# Sheet.net
KiCad netlist of a schematic drawn in Altium Designer
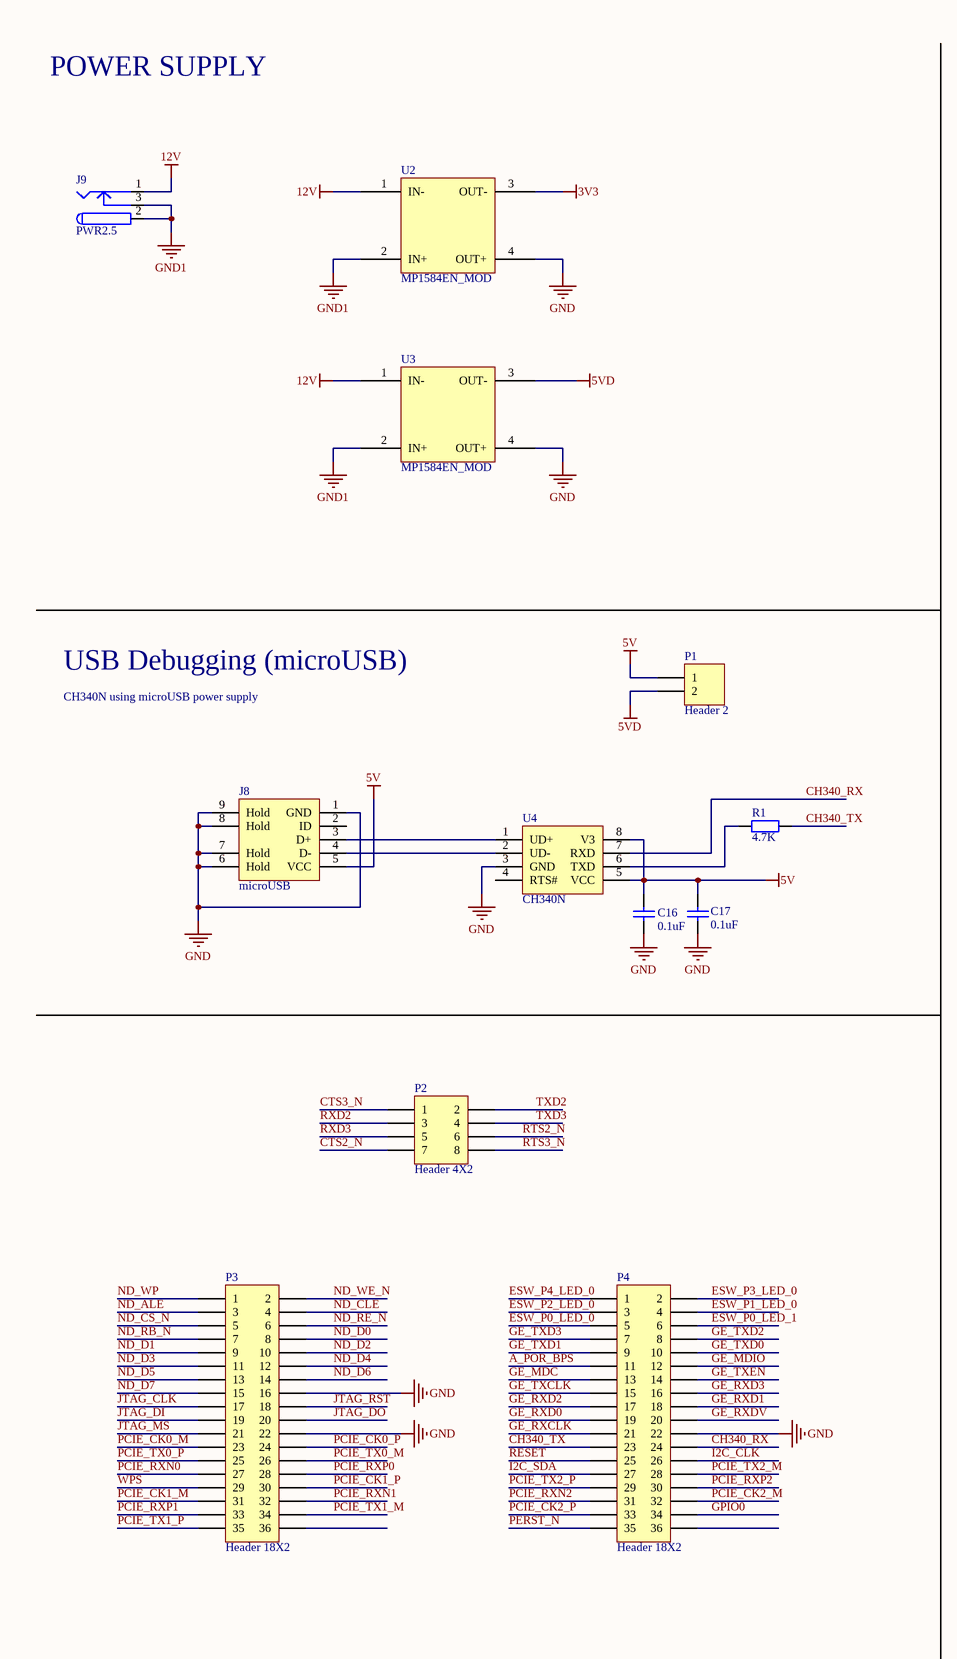
[diagram p0: Sheet.SchDoc, left]
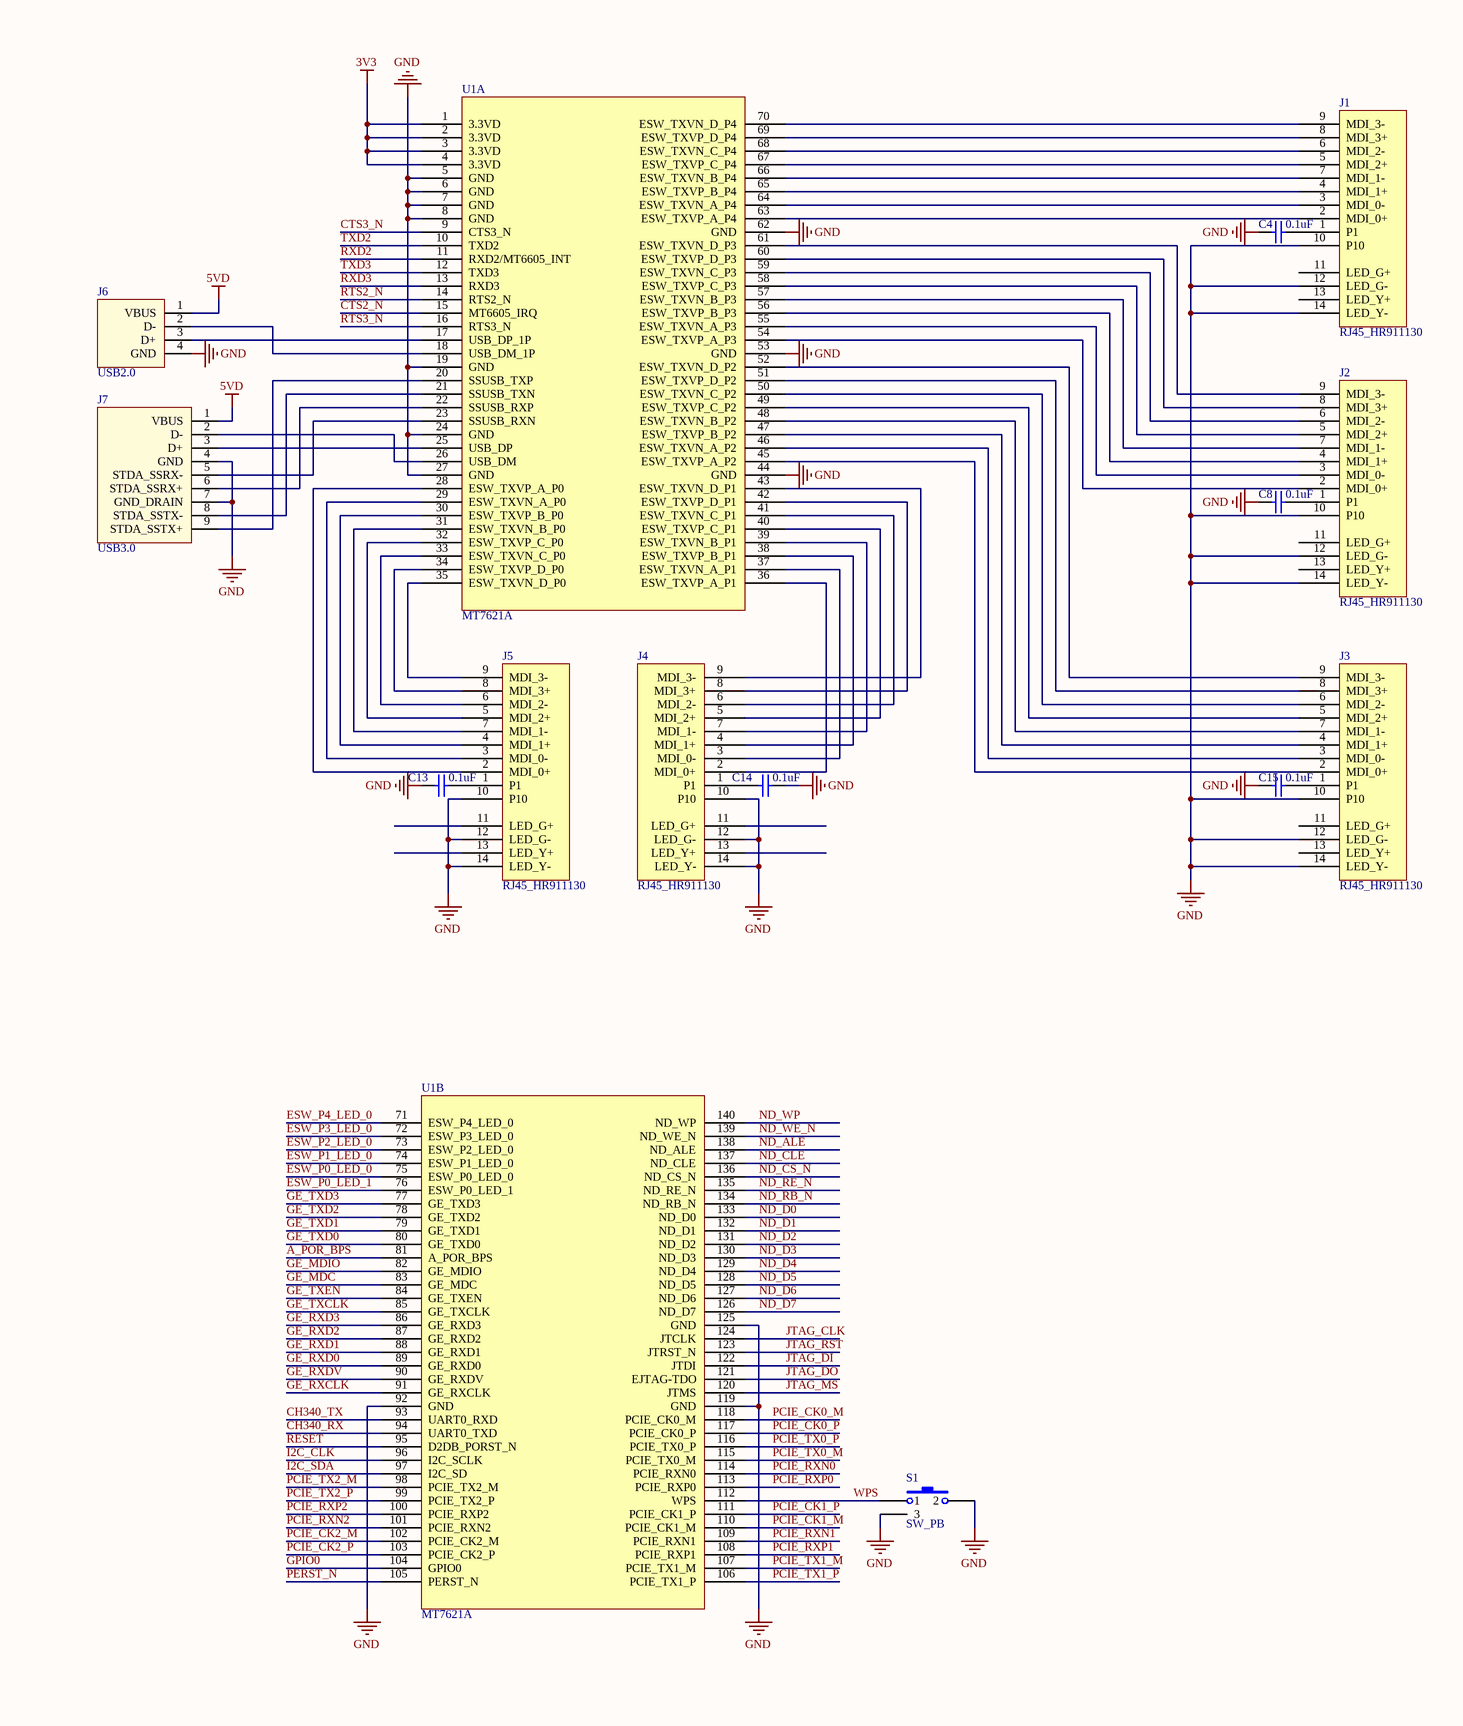
[diagram p1: Sheet.SchDoc, right]

(export (version "E")
  (design (tool "Eeschema 10.0.6"))
  (components
    (comp (ref "C4")
      (value "0.1uF")
      (footprint "C0603")
      (description "Capacitor")
      (fields (field (name "Comment") "Cap") (field (name "PUBLISHER") "Altium Limited"))
      (libsource (lib "Miscellaneous Devices") (part "Cap"))
    )
    (comp (ref "C8")
      (value "0.1uF")
      (footprint "C0603")
      (description "Capacitor")
      (fields (field (name "Comment") "Cap") (field (name "PUBLISHER") "Altium Limited"))
      (libsource (lib "Miscellaneous Devices") (part "Cap"))
    )
    (comp (ref "C13")
      (value "0.1uF")
      (footprint "C0603")
      (description "Capacitor")
      (fields (field (name "Comment") "Cap") (field (name "PUBLISHER") "Altium Limited"))
      (libsource (lib "Miscellaneous Devices") (part "Cap"))
    )
    (comp (ref "C14")
      (value "0.1uF")
      (footprint "C0603")
      (description "Capacitor")
      (fields (field (name "Comment") "Cap") (field (name "PUBLISHER") "Altium Limited"))
      (libsource (lib "Miscellaneous Devices") (part "Cap"))
    )
    (comp (ref "C15")
      (value "0.1uF")
      (footprint "C0603")
      (description "Capacitor")
      (fields (field (name "Comment") "Cap") (field (name "PUBLISHER") "Altium Limited"))
      (libsource (lib "Miscellaneous Devices") (part "Cap"))
    )
    (comp (ref "C16")
      (value "0.1uF")
      (footprint "C0603")
      (description "Capacitor")
      (fields (field (name "Comment") "Cap") (field (name "PUBLISHER") "Altium Limited"))
      (libsource (lib "Miscellaneous Devices") (part "Cap"))
    )
    (comp (ref "C17")
      (value "0.1uF")
      (footprint "C0603")
      (description "Capacitor")
      (fields (field (name "Comment") "Cap") (field (name "PUBLISHER") "Altium Limited"))
      (libsource (lib "Miscellaneous Devices") (part "Cap"))
    )
    (comp (ref "J1")
      (value "RJ45_HR911130")
      (footprint "RJ45_HR911130")
      (libsource (lib "") (part "RJ45_HR911130_1"))
    )
    (comp (ref "J2")
      (value "RJ45_HR911130")
      (footprint "RJ45_HR911130")
      (libsource (lib "") (part "RJ45_HR911130_1"))
    )
    (comp (ref "J3")
      (value "RJ45_HR911130")
      (footprint "RJ45_HR911130")
      (libsource (lib "") (part "RJ45_HR911130_1"))
    )
    (comp (ref "J4")
      (value "RJ45_HR911130")
      (footprint "RJ45_HR911130")
      (libsource (lib "7621_cmp") (part "RJ45_HR911130"))
    )
    (comp (ref "J5")
      (value "RJ45_HR911130")
      (footprint "RJ45_HR911130")
      (libsource (lib "") (part "RJ45_HR911130_1"))
    )
    (comp (ref "J6") (value "USB2.0") (footprint "USB2.0") (libsource (lib "7621_cmp") (part "USB2.0")))
    (comp (ref "J7") (value "USB3.0") (footprint "USB3.0") (libsource (lib "7621_cmp") (part "USB3.0")))
    (comp (ref "J8") (value "microUSB") (footprint "MICROusb") (libsource (lib "7621_cmp") (part "microUSB")))
    (comp (ref "J9")
      (value "PWR2.5")
      (footprint "CON\\DC-JACK\\4.7")
      (libsource (lib "7621_cmp") (part "PWR2.5"))
    )
    (comp (ref "P1")
      (value "Header 2")
      (footprint "HDR1X2")
      (description "Header, 2-Pin")
      (fields (field (name "PUBLISHER") "Altium Limited"))
      (libsource (lib "Miscellaneous Connectors") (part "Header 2"))
    )
    (comp (ref "P2")
      (value "Header 4X2")
      (footprint "HDR2X4")
      (description "Header, 4-Pin, Dual row")
      (fields (field (name "PUBLISHER") "Altium Limited"))
      (libsource (lib "Miscellaneous Connectors") (part "Header 4X2"))
    )
    (comp (ref "P3")
      (value "Header 18X2")
      (footprint "HDR2X18")
      (description "Header, 18-Pin, Dual row")
      (fields (field (name "PUBLISHER") "Altium Limited"))
      (libsource (lib "Miscellaneous Connectors") (part "Header 18X2"))
    )
    (comp (ref "P4")
      (value "Header 18X2")
      (footprint "HDR2X18")
      (description "Header, 18-Pin, Dual row")
      (fields (field (name "PUBLISHER") "Altium Limited"))
      (libsource (lib "Miscellaneous Connectors") (part "Header 18X2"))
    )
    (comp (ref "R1")
      (value "4.7K")
      (footprint "3-0603")
      (description "Resistor")
      (fields (field (name "Comment") "Res2") (field (name "PUBLISHER") "Altium Limited"))
      (libsource (lib "Miscellaneous Devices") (part "Res2"))
    )
    (comp (ref "S1") (value "SW_PB") (footprint "SW_PB") (libsource (lib "7621_cmp") (part "SW_PB")))
    (comp (ref "U1") (value "MT7621A") (footprint "HLK-7621") (libsource (lib "7621_cmp") (part "MT7621A")))
    (comp (ref "U2")
      (value "MP1584EN_MOD")
      (footprint "MP1584EN_MOD")
      (libsource (lib "7621_cmp") (part "MP1584EN_MOD"))
    )
    (comp (ref "U3")
      (value "MP1584EN_MOD")
      (footprint "MP1584EN_MOD")
      (libsource (lib "7621_cmp") (part "MP1584EN_MOD"))
    )
    (comp (ref "U4") (value "CH340N") (footprint "CH340N") (libsource (lib "7621_cmp") (part "CH340N")))
  )
  (nets
    (net (code "1") (name "/A_POR_BPS") (class "Default")
      (node (ref "P4") (pin "11") (pinfunction "11_11") (pintype "passive"))
      (node (ref "U1") (pin "81") (pinfunction "A_POR_BPS_81") (pintype "passive"))
    )
    (net (code "2") (name "/CH340_RX") (class "Default")
      (node (ref "P4") (pin "24") (pinfunction "24_24") (pintype "passive"))
      (node (ref "U1") (pin "94") (pinfunction "UART0_TXD_94") (pintype "passive"))
      (node (ref "U4") (pin "7") (pinfunction "RXD_7") (pintype "passive"))
    )
    (net (code "3") (name "/CH340_TX") (class "Default")
      (node (ref "P4") (pin "23") (pinfunction "23_23") (pintype "passive"))
      (node (ref "R1") (pin "1") (pinfunction "1_1") (pintype "passive"))
      (node (ref "U1") (pin "93") (pinfunction "UART0_RXD_93") (pintype "passive"))
    )
    (net (code "4") (name "/CTS2_N") (class "Default")
      (node (ref "P2") (pin "7") (pinfunction "7_7") (pintype "passive"))
      (node (ref "U1") (pin "15") (pinfunction "MT6605_IRQ_15") (pintype "passive"))
    )
    (net (code "5") (name "/CTS3_N") (class "Default")
      (node (ref "P2") (pin "1") (pinfunction "1_1") (pintype "passive"))
      (node (ref "U1") (pin "9") (pinfunction "CTS3_N_9") (pintype "passive"))
    )
    (net (code "6") (name "/ESW_P0_LED_0") (class "Default")
      (node (ref "P4") (pin "5") (pinfunction "5_5") (pintype "passive"))
      (node (ref "U1") (pin "75") (pinfunction "ESW_P0_LED_0_75") (pintype "passive"))
    )
    (net (code "7") (name "/ESW_P0_LED_1") (class "Default")
      (node (ref "P4") (pin "6") (pinfunction "6_6") (pintype "passive"))
      (node (ref "U1") (pin "76") (pinfunction "ESW_P0_LED_1_76") (pintype "passive"))
    )
    (net (code "8") (name "/ESW_P1_LED_0") (class "Default")
      (node (ref "P4") (pin "4") (pinfunction "4_4") (pintype "passive"))
      (node (ref "U1") (pin "74") (pinfunction "ESW_P1_LED_0_74") (pintype "passive"))
    )
    (net (code "9") (name "/ESW_P2_LED_0") (class "Default")
      (node (ref "P4") (pin "3") (pinfunction "3_3") (pintype "passive"))
      (node (ref "U1") (pin "73") (pinfunction "ESW_P2_LED_0_73") (pintype "passive"))
    )
    (net (code "10") (name "/ESW_P3_LED_0") (class "Default")
      (node (ref "P4") (pin "2") (pinfunction "2_2") (pintype "passive"))
      (node (ref "U1") (pin "72") (pinfunction "ESW_P3_LED_0_72") (pintype "passive"))
    )
    (net (code "11") (name "/ESW_P4_LED_0") (class "Default")
      (node (ref "P4") (pin "1") (pinfunction "1_1") (pintype "passive"))
      (node (ref "U1") (pin "71") (pinfunction "ESW_P4_LED_0_71") (pintype "passive"))
    )
    (net (code "12") (name "/GE_MDC") (class "Default")
      (node (ref "P4") (pin "13") (pinfunction "13_13") (pintype "passive"))
      (node (ref "U1") (pin "83") (pinfunction "GE_MDC_83") (pintype "passive"))
    )
    (net (code "13") (name "/GE_MDIO") (class "Default")
      (node (ref "P4") (pin "12") (pinfunction "12_12") (pintype "passive"))
      (node (ref "U1") (pin "82") (pinfunction "GE_MDIO_82") (pintype "passive"))
    )
    (net (code "14") (name "/GE_RXCLK") (class "Default")
      (node (ref "P4") (pin "21") (pinfunction "21_21") (pintype "passive"))
      (node (ref "U1") (pin "91") (pinfunction "GE_RXCLK_91") (pintype "passive"))
    )
    (net (code "15") (name "/GE_RXD0") (class "Default")
      (node (ref "P4") (pin "19") (pinfunction "19_19") (pintype "passive"))
      (node (ref "U1") (pin "89") (pinfunction "GE_RXD0_89") (pintype "passive"))
    )
    (net (code "16") (name "/GE_RXD1") (class "Default")
      (node (ref "P4") (pin "18") (pinfunction "18_18") (pintype "passive"))
      (node (ref "U1") (pin "88") (pinfunction "GE_RXD1_88") (pintype "passive"))
    )
    (net (code "17") (name "/GE_RXD2") (class "Default")
      (node (ref "P4") (pin "17") (pinfunction "17_17") (pintype "passive"))
      (node (ref "U1") (pin "87") (pinfunction "GE_RXD2_87") (pintype "passive"))
    )
    (net (code "18") (name "/GE_RXD3") (class "Default")
      (node (ref "P4") (pin "16") (pinfunction "16_16") (pintype "passive"))
      (node (ref "U1") (pin "86") (pinfunction "GE_RXD3_86") (pintype "passive"))
    )
    (net (code "19") (name "/GE_RXDV") (class "Default")
      (node (ref "P4") (pin "20") (pinfunction "20_20") (pintype "passive"))
      (node (ref "U1") (pin "90") (pinfunction "GE_RXDV_90") (pintype "passive"))
    )
    (net (code "20") (name "/GE_TXCLK") (class "Default")
      (node (ref "P4") (pin "15") (pinfunction "15_15") (pintype "passive"))
      (node (ref "U1") (pin "85") (pinfunction "GE_TXCLK_85") (pintype "passive"))
    )
    (net (code "21") (name "/GE_TXD0") (class "Default")
      (node (ref "P4") (pin "10") (pinfunction "10_10") (pintype "passive"))
      (node (ref "U1") (pin "80") (pinfunction "GE_TXD0_80") (pintype "passive"))
    )
    (net (code "22") (name "/GE_TXD1") (class "Default")
      (node (ref "P4") (pin "9") (pinfunction "9_9") (pintype "passive"))
      (node (ref "U1") (pin "79") (pinfunction "GE_TXD1_79") (pintype "passive"))
    )
    (net (code "23") (name "/GE_TXD2") (class "Default")
      (node (ref "P4") (pin "8") (pinfunction "8_8") (pintype "passive"))
      (node (ref "U1") (pin "78") (pinfunction "GE_TXD2_78") (pintype "passive"))
    )
    (net (code "24") (name "/GE_TXD3") (class "Default")
      (node (ref "P4") (pin "7") (pinfunction "7_7") (pintype "passive"))
      (node (ref "U1") (pin "77") (pinfunction "GE_TXD3_77") (pintype "passive"))
    )
    (net (code "25") (name "/GE_TXEN") (class "Default")
      (node (ref "P4") (pin "14") (pinfunction "14_14") (pintype "passive"))
      (node (ref "U1") (pin "84") (pinfunction "GE_TXEN_84") (pintype "passive"))
    )
    (net (code "26") (name "/GPIO0") (class "Default")
      (node (ref "P4") (pin "34") (pinfunction "34_34") (pintype "passive"))
      (node (ref "U1") (pin "104") (pinfunction "GPIO0_104") (pintype "passive"))
    )
    (net (code "27") (name "/I2C_CLK") (class "Default")
      (node (ref "P4") (pin "26") (pinfunction "26_26") (pintype "passive"))
      (node (ref "U1") (pin "96") (pinfunction "I2C_SCLK_96") (pintype "passive"))
    )
    (net (code "28") (name "/I2C_SDA") (class "Default")
      (node (ref "P4") (pin "27") (pinfunction "27_27") (pintype "passive"))
      (node (ref "U1") (pin "97") (pinfunction "I2C_SD_97") (pintype "passive"))
    )
    (net (code "29") (name "/JTAG_CLK") (class "Default")
      (node (ref "P3") (pin "17") (pinfunction "17_17") (pintype "passive"))
      (node (ref "U1") (pin "124") (pinfunction "JTCLK_124") (pintype "passive"))
    )
    (net (code "30") (name "/JTAG_DI") (class "Default")
      (node (ref "P3") (pin "19") (pinfunction "19_19") (pintype "passive"))
      (node (ref "U1") (pin "122") (pinfunction "JTDI_122") (pintype "passive"))
    )
    (net (code "31") (name "/JTAG_DO") (class "Default")
      (node (ref "P3") (pin "20") (pinfunction "20_20") (pintype "passive"))
      (node (ref "U1") (pin "121") (pinfunction "EJTAG-TDO_121") (pintype "passive"))
    )
    (net (code "32") (name "/JTAG_MS") (class "Default")
      (node (ref "P3") (pin "21") (pinfunction "21_21") (pintype "passive"))
      (node (ref "U1") (pin "120") (pinfunction "JTMS_120") (pintype "passive"))
    )
    (net (code "33") (name "/JTAG_RST") (class "Default")
      (node (ref "P3") (pin "18") (pinfunction "18_18") (pintype "passive"))
      (node (ref "U1") (pin "123") (pinfunction "JTRST_N_123") (pintype "passive"))
    )
    (net (code "34") (name "/ND_ALE") (class "Default")
      (node (ref "P3") (pin "3") (pinfunction "3_3") (pintype "passive"))
      (node (ref "U1") (pin "138") (pinfunction "ND_ALE_138") (pintype "passive"))
    )
    (net (code "35") (name "/ND_CLE") (class "Default")
      (node (ref "P3") (pin "4") (pinfunction "4_4") (pintype "passive"))
      (node (ref "U1") (pin "137") (pinfunction "ND_CLE_137") (pintype "passive"))
    )
    (net (code "36") (name "/ND_CS_N") (class "Default")
      (node (ref "P3") (pin "5") (pinfunction "5_5") (pintype "passive"))
      (node (ref "U1") (pin "136") (pinfunction "ND_CS_N_136") (pintype "passive"))
    )
    (net (code "37") (name "/ND_D0") (class "Default")
      (node (ref "P3") (pin "8") (pinfunction "8_8") (pintype "passive"))
      (node (ref "U1") (pin "133") (pinfunction "ND_D0_133") (pintype "passive"))
    )
    (net (code "38") (name "/ND_D1") (class "Default")
      (node (ref "P3") (pin "9") (pinfunction "9_9") (pintype "passive"))
      (node (ref "U1") (pin "132") (pinfunction "ND_D1_132") (pintype "passive"))
    )
    (net (code "39") (name "/ND_D2") (class "Default")
      (node (ref "P3") (pin "10") (pinfunction "10_10") (pintype "passive"))
      (node (ref "U1") (pin "131") (pinfunction "ND_D2_131") (pintype "passive"))
    )
    (net (code "40") (name "/ND_D3") (class "Default")
      (node (ref "P3") (pin "11") (pinfunction "11_11") (pintype "passive"))
      (node (ref "U1") (pin "130") (pinfunction "ND_D3_130") (pintype "passive"))
    )
    (net (code "41") (name "/ND_D4") (class "Default")
      (node (ref "P3") (pin "12") (pinfunction "12_12") (pintype "passive"))
      (node (ref "U1") (pin "129") (pinfunction "ND_D4_129") (pintype "passive"))
    )
    (net (code "42") (name "/ND_D5") (class "Default")
      (node (ref "P3") (pin "13") (pinfunction "13_13") (pintype "passive"))
      (node (ref "U1") (pin "128") (pinfunction "ND_D5_128") (pintype "passive"))
    )
    (net (code "43") (name "/ND_D6") (class "Default")
      (node (ref "P3") (pin "14") (pinfunction "14_14") (pintype "passive"))
      (node (ref "U1") (pin "127") (pinfunction "ND_D6_127") (pintype "passive"))
    )
    (net (code "44") (name "/ND_D7") (class "Default")
      (node (ref "P3") (pin "15") (pinfunction "15_15") (pintype "passive"))
      (node (ref "U1") (pin "126") (pinfunction "ND_D7_126") (pintype "passive"))
    )
    (net (code "45") (name "/ND_RB_N") (class "Default")
      (node (ref "P3") (pin "7") (pinfunction "7_7") (pintype "passive"))
      (node (ref "U1") (pin "134") (pinfunction "ND_RB_N_134") (pintype "passive"))
    )
    (net (code "46") (name "/ND_RE_N") (class "Default")
      (node (ref "P3") (pin "6") (pinfunction "6_6") (pintype "passive"))
      (node (ref "U1") (pin "135") (pinfunction "ND_RE_N_135") (pintype "passive"))
    )
    (net (code "47") (name "/ND_WE_N") (class "Default")
      (node (ref "P3") (pin "2") (pinfunction "2_2") (pintype "passive"))
      (node (ref "U1") (pin "139") (pinfunction "ND_WE_N_139") (pintype "passive"))
    )
    (net (code "48") (name "/ND_WP") (class "Default")
      (node (ref "P3") (pin "1") (pinfunction "1_1") (pintype "passive"))
      (node (ref "U1") (pin "140") (pinfunction "ND_WP_140") (pintype "passive"))
    )
    (net (code "49") (name "/PCIE_CK0_M") (class "Default")
      (node (ref "P3") (pin "23") (pinfunction "23_23") (pintype "passive"))
      (node (ref "U1") (pin "118") (pinfunction "PCIE_CK0_M_118") (pintype "passive"))
    )
    (net (code "50") (name "/PCIE_CK0_P") (class "Default")
      (node (ref "P3") (pin "24") (pinfunction "24_24") (pintype "passive"))
      (node (ref "U1") (pin "117") (pinfunction "PCIE_CK0_P_117") (pintype "passive"))
    )
    (net (code "51") (name "/PCIE_CK1_M") (class "Default")
      (node (ref "P3") (pin "31") (pinfunction "31_31") (pintype "passive"))
      (node (ref "U1") (pin "110") (pinfunction "PCIE_CK1_M_110") (pintype "passive"))
    )
    (net (code "52") (name "/PCIE_CK1_P") (class "Default")
      (node (ref "P3") (pin "30") (pinfunction "30_30") (pintype "passive"))
      (node (ref "U1") (pin "111") (pinfunction "PCIE_CK1_P_111") (pintype "passive"))
    )
    (net (code "53") (name "/PCIE_CK2_M") (class "Default")
      (node (ref "P4") (pin "32") (pinfunction "32_32") (pintype "passive"))
      (node (ref "U1") (pin "102") (pinfunction "PCIE_CK2_M_102") (pintype "passive"))
    )
    (net (code "54") (name "/PCIE_CK2_P") (class "Default")
      (node (ref "P4") (pin "33") (pinfunction "33_33") (pintype "passive"))
      (node (ref "U1") (pin "103") (pinfunction "PCIE_CK2_P_103") (pintype "passive"))
    )
    (net (code "55") (name "/PCIE_RXN0") (class "Default")
      (node (ref "P3") (pin "27") (pinfunction "27_27") (pintype "passive"))
      (node (ref "U1") (pin "114") (pinfunction "PCIE_RXN0_114") (pintype "passive"))
    )
    (net (code "56") (name "/PCIE_RXN1") (class "Default")
      (node (ref "P3") (pin "32") (pinfunction "32_32") (pintype "passive"))
      (node (ref "U1") (pin "109") (pinfunction "PCIE_RXN1_109") (pintype "passive"))
    )
    (net (code "57") (name "/PCIE_RXN2") (class "Default")
      (node (ref "P4") (pin "31") (pinfunction "31_31") (pintype "passive"))
      (node (ref "U1") (pin "101") (pinfunction "PCIE_RXN2_101") (pintype "passive"))
    )
    (net (code "58") (name "/PCIE_RXP0") (class "Default")
      (node (ref "P3") (pin "28") (pinfunction "28_28") (pintype "passive"))
      (node (ref "U1") (pin "113") (pinfunction "PCIE_RXP0_113") (pintype "passive"))
    )
    (net (code "59") (name "/PCIE_RXP1") (class "Default")
      (node (ref "P3") (pin "33") (pinfunction "33_33") (pintype "passive"))
      (node (ref "U1") (pin "108") (pinfunction "PCIE_RXP1_108") (pintype "passive"))
    )
    (net (code "60") (name "/PCIE_RXP2") (class "Default")
      (node (ref "P4") (pin "30") (pinfunction "30_30") (pintype "passive"))
      (node (ref "U1") (pin "100") (pinfunction "PCIE_RXP2_100") (pintype "passive"))
    )
    (net (code "61") (name "/PCIE_TX0_M") (class "Default")
      (node (ref "P3") (pin "26") (pinfunction "26_26") (pintype "passive"))
      (node (ref "U1") (pin "115") (pinfunction "PCIE_TX0_M_115") (pintype "passive"))
    )
    (net (code "62") (name "/PCIE_TX0_P") (class "Default")
      (node (ref "P3") (pin "25") (pinfunction "25_25") (pintype "passive"))
      (node (ref "U1") (pin "116") (pinfunction "PCIE_TX0_P_116") (pintype "passive"))
    )
    (net (code "63") (name "/PCIE_TX1_M") (class "Default")
      (node (ref "P3") (pin "34") (pinfunction "34_34") (pintype "passive"))
      (node (ref "U1") (pin "107") (pinfunction "PCIE_TX1_M_107") (pintype "passive"))
    )
    (net (code "64") (name "/PCIE_TX1_P") (class "Default")
      (node (ref "P3") (pin "35") (pinfunction "35_35") (pintype "passive"))
      (node (ref "U1") (pin "106") (pinfunction "PCIE_TX1_P_106") (pintype "passive"))
    )
    (net (code "65") (name "/PCIE_TX2_M") (class "Default")
      (node (ref "P4") (pin "28") (pinfunction "28_28") (pintype "passive"))
      (node (ref "U1") (pin "98") (pinfunction "PCIE_TX2_M_98") (pintype "passive"))
    )
    (net (code "66") (name "/PCIE_TX2_P") (class "Default")
      (node (ref "P4") (pin "29") (pinfunction "29_29") (pintype "passive"))
      (node (ref "U1") (pin "99") (pinfunction "PCIE_TX2_P_99") (pintype "passive"))
    )
    (net (code "67") (name "/PERST_N") (class "Default")
      (node (ref "P4") (pin "35") (pinfunction "35_35") (pintype "passive"))
      (node (ref "U1") (pin "105") (pinfunction "PERST_N_105") (pintype "passive"))
    )
    (net (code "68") (name "/RESET") (class "Default")
      (node (ref "P4") (pin "25") (pinfunction "25_25") (pintype "passive"))
      (node (ref "U1") (pin "95") (pinfunction "D2DB_PORST_N_95") (pintype "passive"))
    )
    (net (code "69") (name "/RTS2_N") (class "Default")
      (node (ref "P2") (pin "6") (pinfunction "6_6") (pintype "passive"))
      (node (ref "U1") (pin "14") (pinfunction "RTS2_N_14") (pintype "passive"))
    )
    (net (code "70") (name "/RTS3_N") (class "Default")
      (node (ref "P2") (pin "8") (pinfunction "8_8") (pintype "passive"))
      (node (ref "U1") (pin "16") (pinfunction "RTS3_N_16") (pintype "passive"))
    )
    (net (code "71") (name "/RXD2") (class "Default")
      (node (ref "P2") (pin "3") (pinfunction "3_3") (pintype "passive"))
      (node (ref "U1") (pin "11") (pinfunction "RXD2/MT6605_INT_11") (pintype "passive"))
    )
    (net (code "72") (name "/RXD3") (class "Default")
      (node (ref "P2") (pin "5") (pinfunction "5_5") (pintype "passive"))
      (node (ref "U1") (pin "13") (pinfunction "RXD3_13") (pintype "passive"))
    )
    (net (code "73") (name "/TXD2") (class "Default")
      (node (ref "P2") (pin "2") (pinfunction "2_2") (pintype "passive"))
      (node (ref "U1") (pin "10") (pinfunction "TXD2_10") (pintype "passive"))
    )
    (net (code "74") (name "/TXD3") (class "Default")
      (node (ref "P2") (pin "4") (pinfunction "4_4") (pintype "passive"))
      (node (ref "U1") (pin "12") (pinfunction "TXD3_12") (pintype "passive"))
    )
    (net (code "75") (name "/WPS") (class "Default")
      (node (ref "P3") (pin "29") (pinfunction "29_29") (pintype "passive"))
      (node (ref "S1") (pin "1") (pinfunction "1_1") (pintype "passive"))
      (node (ref "U1") (pin "112") (pinfunction "WPS_112") (pintype "passive"))
    )
    (net (code "76") (name "3V3") (class "Default")
      (node (ref "U1") (pin "1") (pinfunction "3.3VD_1") (pintype "passive"))
      (node (ref "U1") (pin "2") (pinfunction "3.3VD_2") (pintype "passive"))
      (node (ref "U1") (pin "3") (pinfunction "3.3VD_3") (pintype "passive"))
      (node (ref "U1") (pin "4") (pinfunction "3.3VD_4") (pintype "passive"))
      (node (ref "U2") (pin "3") (pinfunction "OUT-_3") (pintype "passive"))
    )
    (net (code "77") (name "5V") (class "Default")
      (node (ref "C16") (pin "2") (pinfunction "2_2") (pintype "passive"))
      (node (ref "C17") (pin "1") (pinfunction "1_1") (pintype "passive"))
      (node (ref "J8") (pin "5") (pinfunction "VCC_5") (pintype "passive"))
      (node (ref "P1") (pin "1") (pinfunction "1_1") (pintype "passive"))
      (node (ref "U4") (pin "5") (pinfunction "VCC_5") (pintype "passive"))
      (node (ref "U4") (pin "8") (pinfunction "V3_8") (pintype "passive"))
    )
    (net (code "78") (name "5VD") (class "Default")
      (node (ref "J6") (pin "1") (pinfunction "VBUS_1") (pintype "passive"))
      (node (ref "J7") (pin "1") (pinfunction "VBUS_1") (pintype "passive"))
      (node (ref "P1") (pin "2") (pinfunction "2_2") (pintype "passive"))
      (node (ref "U3") (pin "3") (pinfunction "OUT-_3") (pintype "passive"))
    )
    (net (code "79") (name "12V") (class "Default")
      (node (ref "J9") (pin "1") (pinfunction "1_1") (pintype "power_in"))
      (node (ref "U2") (pin "1") (pinfunction "IN-_1") (pintype "passive"))
      (node (ref "U3") (pin "1") (pinfunction "IN-_1") (pintype "passive"))
    )
    (net (code "80") (name "GND") (class "Default")
      (node (ref "C13") (pin "2") (pinfunction "2_2") (pintype "passive"))
      (node (ref "C14") (pin "1") (pinfunction "1_1") (pintype "passive"))
      (node (ref "C15") (pin "2") (pinfunction "2_2") (pintype "passive"))
      (node (ref "C16") (pin "1") (pinfunction "1_1") (pintype "passive"))
      (node (ref "C17") (pin "2") (pinfunction "2_2") (pintype "passive"))
      (node (ref "C4") (pin "2") (pinfunction "2_2") (pintype "passive"))
      (node (ref "C8") (pin "2") (pinfunction "2_2") (pintype "passive"))
      (node (ref "J1") (pin "10") (pinfunction "P10_10") (pintype "passive"))
      (node (ref "J1") (pin "12") (pinfunction "LED_G-_12") (pintype "passive"))
      (node (ref "J1") (pin "14") (pinfunction "LED_Y-_14") (pintype "passive"))
      (node (ref "J2") (pin "10") (pinfunction "P10_10") (pintype "passive"))
      (node (ref "J2") (pin "12") (pinfunction "LED_G-_12") (pintype "passive"))
      (node (ref "J2") (pin "14") (pinfunction "LED_Y-_14") (pintype "passive"))
      (node (ref "J3") (pin "10") (pinfunction "P10_10") (pintype "passive"))
      (node (ref "J3") (pin "12") (pinfunction "LED_G-_12") (pintype "passive"))
      (node (ref "J3") (pin "14") (pinfunction "LED_Y-_14") (pintype "passive"))
      (node (ref "J4") (pin "10") (pinfunction "P10_10") (pintype "passive"))
      (node (ref "J4") (pin "12") (pinfunction "LED_G-_12") (pintype "passive"))
      (node (ref "J4") (pin "14") (pinfunction "LED_Y-_14") (pintype "passive"))
      (node (ref "J5") (pin "10") (pinfunction "P10_10") (pintype "passive"))
      (node (ref "J5") (pin "12") (pinfunction "LED_G-_12") (pintype "passive"))
      (node (ref "J5") (pin "14") (pinfunction "LED_Y-_14") (pintype "passive"))
      (node (ref "J6") (pin "4") (pinfunction "GND_4") (pintype "passive"))
      (node (ref "J7") (pin "4") (pinfunction "GND_4") (pintype "passive"))
      (node (ref "J7") (pin "7") (pinfunction "GND_DRAIN_7") (pintype "passive"))
      (node (ref "J8") (pin "1") (pinfunction "GND_1") (pintype "passive"))
      (node (ref "J8") (pin "6") (pinfunction "Hold_6") (pintype "passive"))
      (node (ref "J8") (pin "7") (pinfunction "Hold_7") (pintype "passive"))
      (node (ref "J8") (pin "8") (pinfunction "Hold_8") (pintype "passive"))
      (node (ref "J8") (pin "9") (pinfunction "Hold_9") (pintype "passive"))
      (node (ref "P3") (pin "16") (pinfunction "16_16") (pintype "passive"))
      (node (ref "P3") (pin "22") (pinfunction "22_22") (pintype "passive"))
      (node (ref "P4") (pin "22") (pinfunction "22_22") (pintype "passive"))
      (node (ref "S1") (pin "2") (pinfunction "2_2") (pintype "passive"))
      (node (ref "S1") (pin "3") (pinfunction "3_3") (pintype "passive"))
      (node (ref "U1") (pin "119") (pinfunction "GND_119") (pintype "passive"))
      (node (ref "U1") (pin "125") (pinfunction "GND_125") (pintype "passive"))
      (node (ref "U1") (pin "19") (pinfunction "GND_19") (pintype "passive"))
      (node (ref "U1") (pin "24") (pinfunction "GND_24") (pintype "passive"))
      (node (ref "U1") (pin "27") (pinfunction "GND_27") (pintype "passive"))
      (node (ref "U1") (pin "44") (pinfunction "GND_44") (pintype "passive"))
      (node (ref "U1") (pin "5") (pinfunction "GND_5") (pintype "passive"))
      (node (ref "U1") (pin "53") (pinfunction "GND_53") (pintype "passive"))
      (node (ref "U1") (pin "6") (pinfunction "GND_6") (pintype "passive"))
      (node (ref "U1") (pin "62") (pinfunction "GND_62") (pintype "passive"))
      (node (ref "U1") (pin "7") (pinfunction "GND_7") (pintype "passive"))
      (node (ref "U1") (pin "8") (pinfunction "GND_8") (pintype "passive"))
      (node (ref "U1") (pin "92") (pinfunction "GND_92") (pintype "passive"))
      (node (ref "U2") (pin "4") (pinfunction "OUT+_4") (pintype "passive"))
      (node (ref "U3") (pin "4") (pinfunction "OUT+_4") (pintype "passive"))
      (node (ref "U4") (pin "3") (pinfunction "GND_3") (pintype "passive"))
    )
    (net (code "81") (name "GND1") (class "Default")
      (node (ref "J9") (pin "2") (pinfunction "2_2") (pintype "power_in"))
      (node (ref "J9") (pin "3") (pinfunction "3_3") (pintype "power_in"))
      (node (ref "U2") (pin "2") (pinfunction "IN+_2") (pintype "passive"))
      (node (ref "U3") (pin "2") (pinfunction "IN+_2") (pintype "passive"))
    )
    (net (code "82") (name "Net-(J1-MDI_0+)") (class "Default")
      (node (ref "J1") (pin "2") (pinfunction "MDI_0+_2") (pintype "passive"))
      (node (ref "U1") (pin "63") (pinfunction "ESW_TXVP_A_P4_63") (pintype "passive"))
    )
    (net (code "83") (name "Net-(J1-MDI_0-)") (class "Default")
      (node (ref "J1") (pin "3") (pinfunction "MDI_0-_3") (pintype "passive"))
      (node (ref "U1") (pin "64") (pinfunction "ESW_TXVN_A_P4_64") (pintype "passive"))
    )
    (net (code "84") (name "Net-(J1-MDI_1+)") (class "Default")
      (node (ref "J1") (pin "4") (pinfunction "MDI_1+_4") (pintype "passive"))
      (node (ref "U1") (pin "65") (pinfunction "ESW_TXVP_B_P4_65") (pintype "passive"))
    )
    (net (code "85") (name "Net-(J1-MDI_1-)") (class "Default")
      (node (ref "J1") (pin "7") (pinfunction "MDI_1-_7") (pintype "passive"))
      (node (ref "U1") (pin "66") (pinfunction "ESW_TXVN_B_P4_66") (pintype "passive"))
    )
    (net (code "86") (name "Net-(J1-MDI_2+)") (class "Default")
      (node (ref "J1") (pin "5") (pinfunction "MDI_2+_5") (pintype "passive"))
      (node (ref "U1") (pin "67") (pinfunction "ESW_TXVP_C_P4_67") (pintype "passive"))
    )
    (net (code "87") (name "Net-(J1-MDI_2-)") (class "Default")
      (node (ref "J1") (pin "6") (pinfunction "MDI_2-_6") (pintype "passive"))
      (node (ref "U1") (pin "68") (pinfunction "ESW_TXVN_C_P4_68") (pintype "passive"))
    )
    (net (code "88") (name "Net-(J1-MDI_3+)") (class "Default")
      (node (ref "J1") (pin "8") (pinfunction "MDI_3+_8") (pintype "passive"))
      (node (ref "U1") (pin "69") (pinfunction "ESW_TXVP_D_P4_69") (pintype "passive"))
    )
    (net (code "89") (name "Net-(J1-MDI_3-)") (class "Default")
      (node (ref "J1") (pin "9") (pinfunction "MDI_3-_9") (pintype "passive"))
      (node (ref "U1") (pin "70") (pinfunction "ESW_TXVN_D_P4_70") (pintype "passive"))
    )
    (net (code "90") (name "Net-(J1-P1)") (class "Default")
      (node (ref "C4") (pin "1") (pinfunction "1_1") (pintype "passive"))
      (node (ref "J1") (pin "1") (pinfunction "P1_1") (pintype "passive"))
    )
    (net (code "91") (name "Net-(J2-MDI_0+)") (class "Default")
      (node (ref "J2") (pin "2") (pinfunction "MDI_0+_2") (pintype "passive"))
      (node (ref "U1") (pin "54") (pinfunction "ESW_TXVP_A_P3_54") (pintype "passive"))
    )
    (net (code "92") (name "Net-(J2-MDI_0-)") (class "Default")
      (node (ref "J2") (pin "3") (pinfunction "MDI_0-_3") (pintype "passive"))
      (node (ref "U1") (pin "55") (pinfunction "ESW_TXVN_A_P3_55") (pintype "passive"))
    )
    (net (code "93") (name "Net-(J2-MDI_1+)") (class "Default")
      (node (ref "J2") (pin "4") (pinfunction "MDI_1+_4") (pintype "passive"))
      (node (ref "U1") (pin "56") (pinfunction "ESW_TXVP_B_P3_56") (pintype "passive"))
    )
    (net (code "94") (name "Net-(J2-MDI_1-)") (class "Default")
      (node (ref "J2") (pin "7") (pinfunction "MDI_1-_7") (pintype "passive"))
      (node (ref "U1") (pin "57") (pinfunction "ESW_TXVN_B_P3_57") (pintype "passive"))
    )
    (net (code "95") (name "Net-(J2-MDI_2+)") (class "Default")
      (node (ref "J2") (pin "5") (pinfunction "MDI_2+_5") (pintype "passive"))
      (node (ref "U1") (pin "58") (pinfunction "ESW_TXVP_C_P3_58") (pintype "passive"))
    )
    (net (code "96") (name "Net-(J2-MDI_2-)") (class "Default")
      (node (ref "J2") (pin "6") (pinfunction "MDI_2-_6") (pintype "passive"))
      (node (ref "U1") (pin "59") (pinfunction "ESW_TXVN_C_P3_59") (pintype "passive"))
    )
    (net (code "97") (name "Net-(J2-MDI_3+)") (class "Default")
      (node (ref "J2") (pin "8") (pinfunction "MDI_3+_8") (pintype "passive"))
      (node (ref "U1") (pin "60") (pinfunction "ESW_TXVP_D_P3_60") (pintype "passive"))
    )
    (net (code "98") (name "Net-(J2-MDI_3-)") (class "Default")
      (node (ref "J2") (pin "9") (pinfunction "MDI_3-_9") (pintype "passive"))
      (node (ref "U1") (pin "61") (pinfunction "ESW_TXVN_D_P3_61") (pintype "passive"))
    )
    (net (code "99") (name "Net-(J2-P1)") (class "Default")
      (node (ref "C8") (pin "1") (pinfunction "1_1") (pintype "passive"))
      (node (ref "J2") (pin "1") (pinfunction "P1_1") (pintype "passive"))
    )
    (net (code "100") (name "Net-(J3-MDI_0+)") (class "Default")
      (node (ref "J3") (pin "2") (pinfunction "MDI_0+_2") (pintype "passive"))
      (node (ref "U1") (pin "45") (pinfunction "ESW_TXVP_A_P2_45") (pintype "passive"))
    )
    (net (code "101") (name "Net-(J3-MDI_0-)") (class "Default")
      (node (ref "J3") (pin "3") (pinfunction "MDI_0-_3") (pintype "passive"))
      (node (ref "U1") (pin "46") (pinfunction "ESW_TXVN_A_P2_46") (pintype "passive"))
    )
    (net (code "102") (name "Net-(J3-MDI_1+)") (class "Default")
      (node (ref "J3") (pin "4") (pinfunction "MDI_1+_4") (pintype "passive"))
      (node (ref "U1") (pin "47") (pinfunction "ESW_TXVP_B_P2_47") (pintype "passive"))
    )
    (net (code "103") (name "Net-(J3-MDI_1-)") (class "Default")
      (node (ref "J3") (pin "7") (pinfunction "MDI_1-_7") (pintype "passive"))
      (node (ref "U1") (pin "48") (pinfunction "ESW_TXVN_B_P2_48") (pintype "passive"))
    )
    (net (code "104") (name "Net-(J3-MDI_2+)") (class "Default")
      (node (ref "J3") (pin "5") (pinfunction "MDI_2+_5") (pintype "passive"))
      (node (ref "U1") (pin "49") (pinfunction "ESW_TXVP_C_P2_49") (pintype "passive"))
    )
    (net (code "105") (name "Net-(J3-MDI_2-)") (class "Default")
      (node (ref "J3") (pin "6") (pinfunction "MDI_2-_6") (pintype "passive"))
      (node (ref "U1") (pin "50") (pinfunction "ESW_TXVN_C_P2_50") (pintype "passive"))
    )
    (net (code "106") (name "Net-(J3-MDI_3+)") (class "Default")
      (node (ref "J3") (pin "8") (pinfunction "MDI_3+_8") (pintype "passive"))
      (node (ref "U1") (pin "51") (pinfunction "ESW_TXVP_D_P2_51") (pintype "passive"))
    )
    (net (code "107") (name "Net-(J3-MDI_3-)") (class "Default")
      (node (ref "J3") (pin "9") (pinfunction "MDI_3-_9") (pintype "passive"))
      (node (ref "U1") (pin "52") (pinfunction "ESW_TXVN_D_P2_52") (pintype "passive"))
    )
    (net (code "108") (name "Net-(J3-P1)") (class "Default")
      (node (ref "C15") (pin "1") (pinfunction "1_1") (pintype "passive"))
      (node (ref "J3") (pin "1") (pinfunction "P1_1") (pintype "passive"))
    )
    (net (code "109") (name "Net-(J4-MDI_0+)") (class "Default")
      (node (ref "J4") (pin "2") (pinfunction "MDI_0+_2") (pintype "passive"))
      (node (ref "U1") (pin "36") (pinfunction "ESW_TXVP_A_P1_36") (pintype "passive"))
    )
    (net (code "110") (name "Net-(J4-MDI_0-)") (class "Default")
      (node (ref "J4") (pin "3") (pinfunction "MDI_0-_3") (pintype "passive"))
      (node (ref "U1") (pin "37") (pinfunction "ESW_TXVN_A_P1_37") (pintype "passive"))
    )
    (net (code "111") (name "Net-(J4-MDI_1+)") (class "Default")
      (node (ref "J4") (pin "4") (pinfunction "MDI_1+_4") (pintype "passive"))
      (node (ref "U1") (pin "38") (pinfunction "ESW_TXVP_B_P1_38") (pintype "passive"))
    )
    (net (code "112") (name "Net-(J4-MDI_1-)") (class "Default")
      (node (ref "J4") (pin "7") (pinfunction "MDI_1-_7") (pintype "passive"))
      (node (ref "U1") (pin "39") (pinfunction "ESW_TXVN_B_P1_39") (pintype "passive"))
    )
    (net (code "113") (name "Net-(J4-MDI_2+)") (class "Default")
      (node (ref "J4") (pin "5") (pinfunction "MDI_2+_5") (pintype "passive"))
      (node (ref "U1") (pin "40") (pinfunction "ESW_TXVP_C_P1_40") (pintype "passive"))
    )
    (net (code "114") (name "Net-(J4-MDI_2-)") (class "Default")
      (node (ref "J4") (pin "6") (pinfunction "MDI_2-_6") (pintype "passive"))
      (node (ref "U1") (pin "41") (pinfunction "ESW_TXVN_C_P1_41") (pintype "passive"))
    )
    (net (code "115") (name "Net-(J4-MDI_3+)") (class "Default")
      (node (ref "J4") (pin "8") (pinfunction "MDI_3+_8") (pintype "passive"))
      (node (ref "U1") (pin "42") (pinfunction "ESW_TXVP_D_P1_42") (pintype "passive"))
    )
    (net (code "116") (name "Net-(J4-MDI_3-)") (class "Default")
      (node (ref "J4") (pin "9") (pinfunction "MDI_3-_9") (pintype "passive"))
      (node (ref "U1") (pin "43") (pinfunction "ESW_TXVN_D_P1_43") (pintype "passive"))
    )
    (net (code "117") (name "Net-(J4-P1)") (class "Default")
      (node (ref "C14") (pin "2") (pinfunction "2_2") (pintype "passive"))
      (node (ref "J4") (pin "1") (pinfunction "P1_1") (pintype "passive"))
    )
    (net (code "118") (name "Net-(J5-MDI_0+)") (class "Default")
      (node (ref "J5") (pin "2") (pinfunction "MDI_0+_2") (pintype "passive"))
      (node (ref "U1") (pin "28") (pinfunction "ESW_TXVP_A_P0_28") (pintype "passive"))
    )
    (net (code "119") (name "Net-(J5-MDI_0-)") (class "Default")
      (node (ref "J5") (pin "3") (pinfunction "MDI_0-_3") (pintype "passive"))
      (node (ref "U1") (pin "29") (pinfunction "ESW_TXVN_A_P0_29") (pintype "passive"))
    )
    (net (code "120") (name "Net-(J5-MDI_1+)") (class "Default")
      (node (ref "J5") (pin "4") (pinfunction "MDI_1+_4") (pintype "passive"))
      (node (ref "U1") (pin "30") (pinfunction "ESW_TXVP_B_P0_30") (pintype "passive"))
    )
    (net (code "121") (name "Net-(J5-MDI_1-)") (class "Default")
      (node (ref "J5") (pin "7") (pinfunction "MDI_1-_7") (pintype "passive"))
      (node (ref "U1") (pin "31") (pinfunction "ESW_TXVN_B_P0_31") (pintype "passive"))
    )
    (net (code "122") (name "Net-(J5-MDI_2+)") (class "Default")
      (node (ref "J5") (pin "5") (pinfunction "MDI_2+_5") (pintype "passive"))
      (node (ref "U1") (pin "32") (pinfunction "ESW_TXVP_C_P0_32") (pintype "passive"))
    )
    (net (code "123") (name "Net-(J5-MDI_2-)") (class "Default")
      (node (ref "J5") (pin "6") (pinfunction "MDI_2-_6") (pintype "passive"))
      (node (ref "U1") (pin "33") (pinfunction "ESW_TXVN_C_P0_33") (pintype "passive"))
    )
    (net (code "124") (name "Net-(J5-MDI_3+)") (class "Default")
      (node (ref "J5") (pin "8") (pinfunction "MDI_3+_8") (pintype "passive"))
      (node (ref "U1") (pin "34") (pinfunction "ESW_TXVP_D_P0_34") (pintype "passive"))
    )
    (net (code "125") (name "Net-(J5-MDI_3-)") (class "Default")
      (node (ref "J5") (pin "9") (pinfunction "MDI_3-_9") (pintype "passive"))
      (node (ref "U1") (pin "35") (pinfunction "ESW_TXVN_D_P0_35") (pintype "passive"))
    )
    (net (code "126") (name "Net-(J5-P1)") (class "Default")
      (node (ref "C13") (pin "1") (pinfunction "1_1") (pintype "passive"))
      (node (ref "J5") (pin "1") (pinfunction "P1_1") (pintype "passive"))
    )
    (net (code "127") (name "Net-(J6-D+)") (class "Default")
      (node (ref "J6") (pin "3") (pinfunction "D+_3") (pintype "passive"))
      (node (ref "U1") (pin "17") (pinfunction "USB_DP_1P_17") (pintype "passive"))
    )
    (net (code "128") (name "Net-(J6-D-)") (class "Default")
      (node (ref "J6") (pin "2") (pinfunction "D-_2") (pintype "passive"))
      (node (ref "U1") (pin "18") (pinfunction "USB_DM_1P_18") (pintype "passive"))
    )
    (net (code "129") (name "Net-(J7-D+)") (class "Default")
      (node (ref "J7") (pin "3") (pinfunction "D+_3") (pintype "passive"))
      (node (ref "U1") (pin "25") (pinfunction "USB_DP_25") (pintype "passive"))
    )
    (net (code "130") (name "Net-(J7-D-)") (class "Default")
      (node (ref "J7") (pin "2") (pinfunction "D-_2") (pintype "passive"))
      (node (ref "U1") (pin "26") (pinfunction "USB_DM_26") (pintype "passive"))
    )
    (net (code "131") (name "Net-(J7-STDA_SSRX+)") (class "Default")
      (node (ref "J7") (pin "6") (pinfunction "STDA_SSRX+_6") (pintype "passive"))
      (node (ref "U1") (pin "22") (pinfunction "SSUSB_RXP_22") (pintype "passive"))
    )
    (net (code "132") (name "Net-(J7-STDA_SSRX-)") (class "Default")
      (node (ref "J7") (pin "5") (pinfunction "STDA_SSRX-_5") (pintype "passive"))
      (node (ref "U1") (pin "23") (pinfunction "SSUSB_RXN_23") (pintype "passive"))
    )
    (net (code "133") (name "Net-(J7-STDA_SSTX+)") (class "Default")
      (node (ref "J7") (pin "9") (pinfunction "STDA_SSTX+_9") (pintype "passive"))
      (node (ref "U1") (pin "20") (pinfunction "SSUSB_TXP_20") (pintype "passive"))
    )
    (net (code "134") (name "Net-(J7-STDA_SSTX-)") (class "Default")
      (node (ref "J7") (pin "8") (pinfunction "STDA_SSTX-_8") (pintype "passive"))
      (node (ref "U1") (pin "21") (pinfunction "SSUSB_TXN_21") (pintype "passive"))
    )
    (net (code "135") (name "Net-(J8-D+)") (class "Default")
      (node (ref "J8") (pin "3") (pinfunction "D+_3") (pintype "passive"))
      (node (ref "U4") (pin "1") (pinfunction "UD+_1") (pintype "passive"))
    )
    (net (code "136") (name "Net-(J8-D-)") (class "Default")
      (node (ref "J8") (pin "4") (pinfunction "D-_4") (pintype "passive"))
      (node (ref "U4") (pin "2") (pinfunction "UD-_2") (pintype "passive"))
    )
    (net (code "137") (name "Net-(U4-TXD)") (class "Default")
      (node (ref "R1") (pin "2") (pinfunction "2_2") (pintype "passive"))
      (node (ref "U4") (pin "6") (pinfunction "TXD_6") (pintype "passive"))
    )
    (net (code "138") (name "unconnected-(J1-LED_G+-Pad11)") (class "Default")
      (node (ref "J1") (pin "11") (pinfunction "LED_G+_11") (pintype "passive"))
    )
    (net (code "139") (name "unconnected-(J1-LED_Y+-Pad13)") (class "Default")
      (node (ref "J1") (pin "13") (pinfunction "LED_Y+_13") (pintype "passive"))
    )
    (net (code "140") (name "unconnected-(J2-LED_G+-Pad11)") (class "Default")
      (node (ref "J2") (pin "11") (pinfunction "LED_G+_11") (pintype "passive"))
    )
    (net (code "141") (name "unconnected-(J2-LED_Y+-Pad13)") (class "Default")
      (node (ref "J2") (pin "13") (pinfunction "LED_Y+_13") (pintype "passive"))
    )
    (net (code "142") (name "unconnected-(J3-LED_G+-Pad11)") (class "Default")
      (node (ref "J3") (pin "11") (pinfunction "LED_G+_11") (pintype "passive"))
    )
    (net (code "143") (name "unconnected-(J3-LED_Y+-Pad13)") (class "Default")
      (node (ref "J3") (pin "13") (pinfunction "LED_Y+_13") (pintype "passive"))
    )
    (net (code "144") (name "unconnected-(J4-LED_G+-Pad11)") (class "Default")
      (node (ref "J4") (pin "11") (pinfunction "LED_G+_11") (pintype "passive"))
    )
    (net (code "145") (name "unconnected-(J4-LED_Y+-Pad13)") (class "Default")
      (node (ref "J4") (pin "13") (pinfunction "LED_Y+_13") (pintype "passive"))
    )
    (net (code "146") (name "unconnected-(J5-LED_G+-Pad11)") (class "Default")
      (node (ref "J5") (pin "11") (pinfunction "LED_G+_11") (pintype "passive"))
    )
    (net (code "147") (name "unconnected-(J5-LED_Y+-Pad13)") (class "Default")
      (node (ref "J5") (pin "13") (pinfunction "LED_Y+_13") (pintype "passive"))
    )
    (net (code "148") (name "unconnected-(J8-ID-Pad2)") (class "Default")
      (node (ref "J8") (pin "2") (pinfunction "ID_2") (pintype "passive"))
    )
    (net (code "149") (name "unconnected-(P3-Pad36)") (class "Default")
      (node (ref "P3") (pin "36") (pinfunction "36_36") (pintype "passive"))
    )
    (net (code "150") (name "unconnected-(P4-Pad36)") (class "Default")
      (node (ref "P4") (pin "36") (pinfunction "36_36") (pintype "passive"))
    )
    (net (code "151") (name "unconnected-(U4-RTS#-Pad4)") (class "Default")
      (node (ref "U4") (pin "4") (pinfunction "RTS#_4") (pintype "passive"))
    )
  )
)
